# TFDU4101_Connection_Schematic.net
KiCad netlist of a schematic drawn in EAGLE
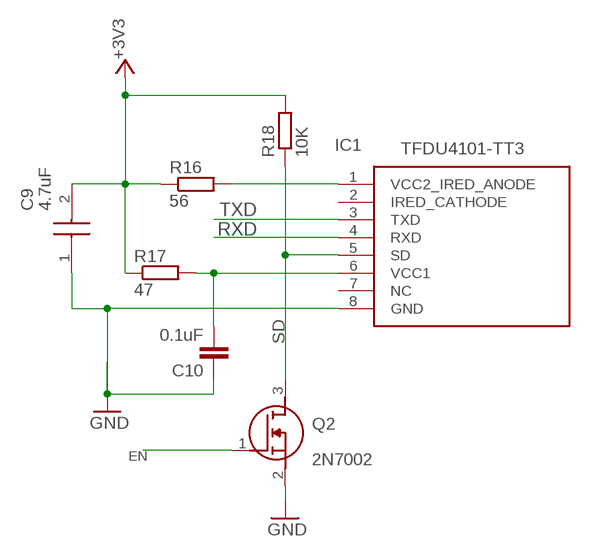
[diagram p0: schematic, sheet 1]

(export (version "E")
  (design (tool "Eeschema 10.0.6"))
  (components
    (comp (ref "C9")
      (value "4.7uF")
      (footprint "eagle-import:CAPC2012X135N")
      (fields (field (name "MANUFACTURER_PART_NUMBER") "CL21A475KPFNNNG"))
      (libsource (lib "eagle-import") (part "CL21A475KPFNNNG"))
    )
    (comp (ref "C10")
      (value "0.1uF")
      (footprint "eagle-import:C0805")
      (libsource (lib "eagle-import") (part "C-EUC0805"))
    )
    (comp (ref "IC1")
      (value "TFDU4101-TT3")
      (footprint "eagle-import:TFDU4101-TR3")
      (fields (field (name "MOUSER_PART_NUMBER") "782-TFDU4101-TT3"))
      (libsource (lib "eagle-import") (part "TFDU4101-TT3"))
    )
    (comp (ref "Q2")
      (value "2N7002")
      (footprint "eagle-import:SOT96P240X120-3N")
      (fields (field (name "MOUSER_PART_NUMBER") "512-2N7002"))
      (libsource (lib "eagle-import") (part "2N7002"))
    )
    (comp (ref "R16")
      (value "56")
      (footprint "eagle-import:R0805")
      (libsource (lib "eagle-import") (part "R-EU_R0805"))
    )
    (comp (ref "R17")
      (value "47")
      (footprint "eagle-import:R0805")
      (libsource (lib "eagle-import") (part "R-EU_R0805"))
    )
    (comp (ref "R18")
      (value "10K")
      (footprint "eagle-import:R0805")
      (libsource (lib "eagle-import") (part "R-EU_R0805"))
    )
  )
  (nets
    (net (code "1") (name "+3V3") (class "Default")
      (node (ref "C9") (pin "2") (pinfunction "2_2") (pintype "bidirectional"))
      (node (ref "R16") (pin "1") (pinfunction "1_1") (pintype "passive"))
      (node (ref "R17") (pin "1") (pinfunction "1_1") (pintype "passive"))
      (node (ref "R18") (pin "2") (pinfunction "2_2") (pintype "passive"))
    )
    (net (code "2") (name "/EN") (class "Default")
      (node (ref "Q2") (pin "1") (pinfunction "G_1") (pintype "bidirectional"))
    )
    (net (code "3") (name "/RXD") (class "Default")
      (node (ref "IC1") (pin "4") (pinfunction "RXD_4") (pintype "bidirectional"))
    )
    (net (code "4") (name "/SD") (class "Default")
      (node (ref "IC1") (pin "5") (pinfunction "SD_5") (pintype "bidirectional"))
      (node (ref "Q2") (pin "3") (pinfunction "D_3") (pintype "bidirectional"))
      (node (ref "R18") (pin "1") (pinfunction "1_1") (pintype "passive"))
    )
    (net (code "5") (name "/TXD") (class "Default")
      (node (ref "IC1") (pin "3") (pinfunction "TXD_3") (pintype "bidirectional"))
    )
    (net (code "6") (name "GND") (class "Default")
      (node (ref "C10") (pin "1") (pinfunction "1_1") (pintype "passive"))
      (node (ref "C9") (pin "1") (pinfunction "1_1") (pintype "bidirectional"))
      (node (ref "IC1") (pin "8") (pinfunction "GND_8") (pintype "bidirectional"))
      (node (ref "Q2") (pin "2") (pinfunction "S_2") (pintype "bidirectional"))
    )
    (net (code "7") (name "Net-(IC1-VCC1)") (class "Default")
      (node (ref "C10") (pin "2") (pinfunction "2_2") (pintype "passive"))
      (node (ref "IC1") (pin "6") (pinfunction "VCC1_6") (pintype "bidirectional"))
      (node (ref "R17") (pin "2") (pinfunction "2_2") (pintype "passive"))
    )
    (net (code "8") (name "Net-(IC1-VCC2_IRED_ANODE)") (class "Default")
      (node (ref "IC1") (pin "1") (pinfunction "VCC2_IRED_ANODE_1") (pintype "bidirectional"))
      (node (ref "R16") (pin "2") (pinfunction "2_2") (pintype "passive"))
    )
    (net (code "9") (name "unconnected-(IC1-IRED_CATHODE-Pad2)") (class "Default")
      (node (ref "IC1") (pin "2") (pinfunction "IRED_CATHODE_2") (pintype "bidirectional"))
    )
    (net (code "10") (name "unconnected-(IC1-NC-Pad7)") (class "Default")
      (node (ref "IC1") (pin "7") (pinfunction "NC_7") (pintype "no_connect"))
    )
  )
)
